# TMK-EURO.net
KiCad netlist of a schematic drawn in EAGLE
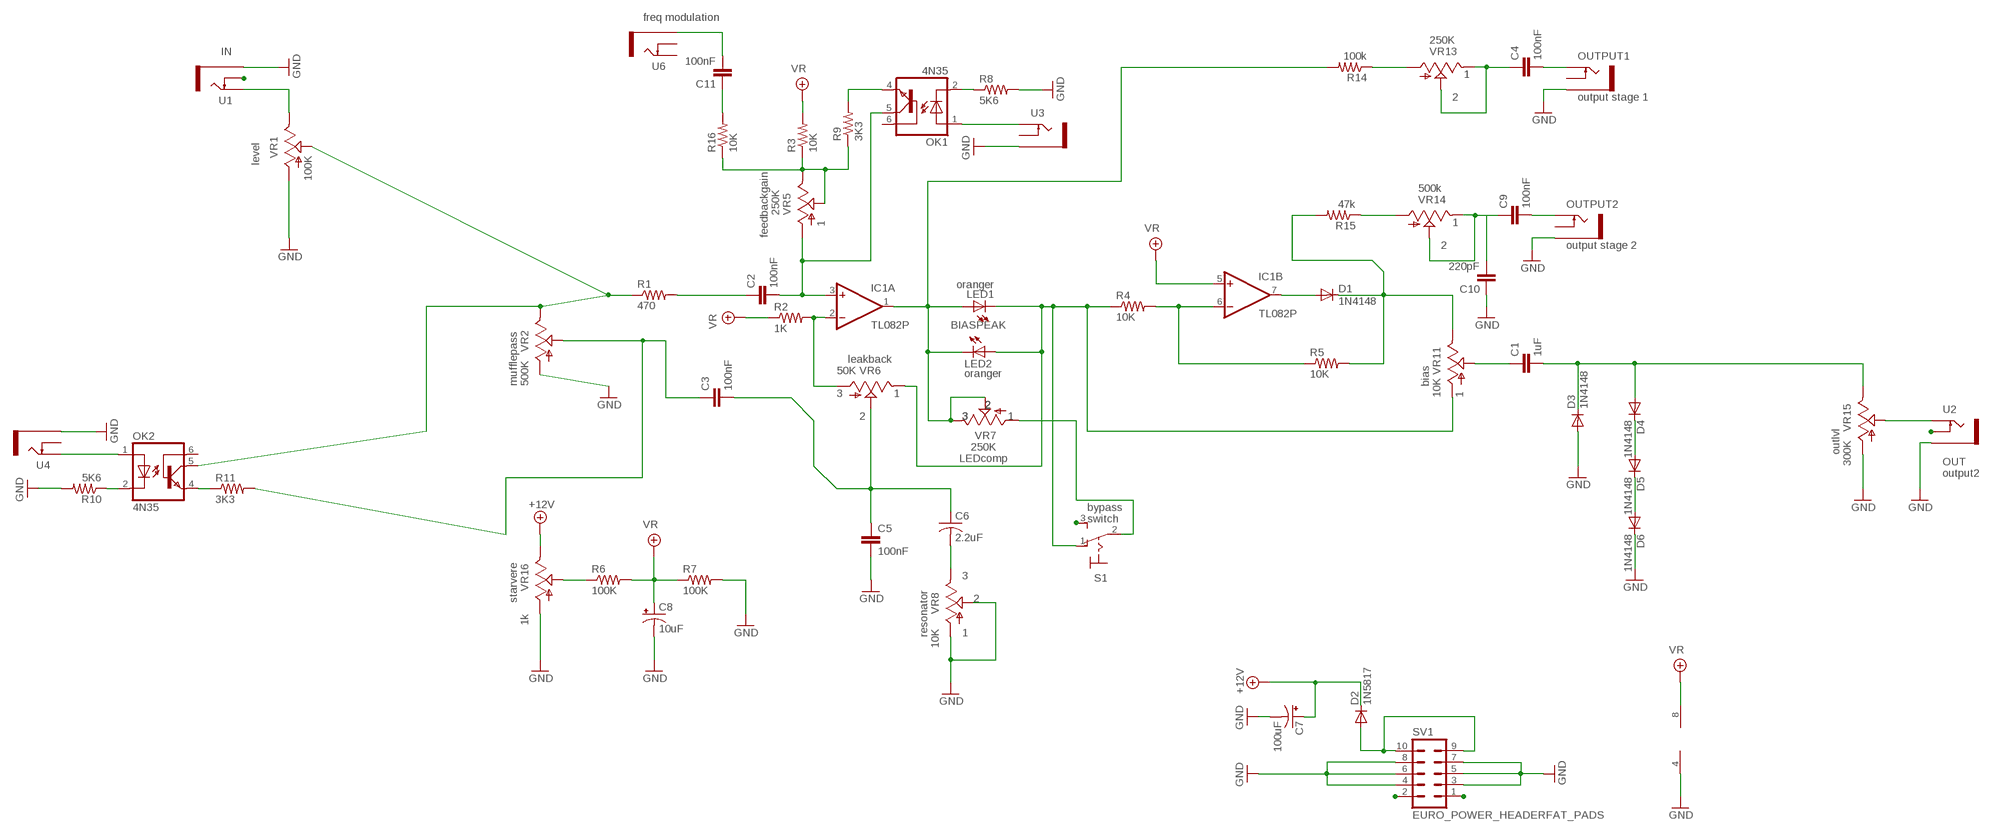
[diagram p0: schematic, sheet 1]

(export (version "E")
  (design (tool "Eeschema 10.0.6"))
  (components
    (comp (ref "C1")
      (value "1uF")
      (footprint "eagle-import:C050-035X075")
      (libsource (lib "eagle-import") (part "C-EU050-035X075"))
    )
    (comp (ref "C2")
      (value "100nF")
      (footprint "eagle-import:C050-035X075")
      (libsource (lib "eagle-import") (part "C-EU050-035X075"))
    )
    (comp (ref "C3")
      (value "100nF")
      (footprint "eagle-import:C050-035X075")
      (libsource (lib "eagle-import") (part "C-EU050-035X075"))
    )
    (comp (ref "C4")
      (value "100nF")
      (footprint "eagle-import:C050-035X075")
      (libsource (lib "eagle-import") (part "C-EU050-035X075"))
    )
    (comp (ref "C5")
      (value "100nF")
      (footprint "eagle-import:C050-035X075")
      (libsource (lib "eagle-import") (part "C-EU050-035X075"))
    )
    (comp (ref "C6")
      (value "2.2uF")
      (footprint "eagle-import:C050-030X075")
      (libsource (lib "eagle-import") (part "C-US050-030X075"))
    )
    (comp (ref "C7")
      (value "100uF")
      (footprint "eagle-import:E2-5")
      (libsource (lib "eagle-import") (part "CPOL-USE2-5"))
    )
    (comp (ref "C8")
      (value "10uF")
      (footprint "eagle-import:E2-5")
      (libsource (lib "eagle-import") (part "CPOL-USE2-5"))
    )
    (comp (ref "C9")
      (value "100nF")
      (footprint "eagle-import:C050-035X075")
      (libsource (lib "eagle-import") (part "C-EU050-035X075"))
    )
    (comp (ref "C10")
      (value "220pF")
      (footprint "eagle-import:C050-035X075")
      (libsource (lib "eagle-import") (part "C-EU050-035X075"))
    )
    (comp (ref "C11")
      (value "100nF")
      (footprint "eagle-import:C050-035X075")
      (libsource (lib "eagle-import") (part "C-EU050-035X075"))
    )
    (comp (ref "D1")
      (value "1N4148")
      (footprint "eagle-import:DO35-7")
      (libsource (lib "eagle-import") (part "SMALL_DIODEDO35-7"))
    )
    (comp (ref "D2")
      (value "1N5817")
      (footprint "eagle-import:DO35-7")
      (libsource (lib "eagle-import") (part "SMALL_DIODEDO35-7"))
    )
    (comp (ref "D3")
      (value "1N4148")
      (footprint "eagle-import:DO35-7")
      (libsource (lib "eagle-import") (part "SMALL_DIODEDO35-7"))
    )
    (comp (ref "D4")
      (value "1N4148")
      (footprint "eagle-import:DO35-7")
      (libsource (lib "eagle-import") (part "SMALL_DIODEDO35-7"))
    )
    (comp (ref "D5")
      (value "1N4148")
      (footprint "eagle-import:DO35-7")
      (libsource (lib "eagle-import") (part "SMALL_DIODEDO35-7"))
    )
    (comp (ref "D6")
      (value "1N4148")
      (footprint "eagle-import:DO35-7")
      (libsource (lib "eagle-import") (part "SMALL_DIODEDO35-7"))
    )
    (comp (ref "IC1")
      (value "TL082P")
      (footprint "eagle-import:DIL08")
      (libsource (lib "eagle-import") (part "TL082P"))
    )
    (comp (ref "LED1")
      (value "oranger")
      (footprint "eagle-import:LED3MM")
      (libsource (lib "eagle-import") (part "LED3MM"))
    )
    (comp (ref "LED2")
      (value "oranger")
      (footprint "eagle-import:LED3MM")
      (libsource (lib "eagle-import") (part "LED3MM"))
    )
    (comp (ref "OK1")
      (value "4N35")
      (footprint "eagle-import:DIL06")
      (fields (field (name "MF") "FAIRCHILD SEMICONDUCTOR"))
      (libsource (lib "eagle-import") (part "4N35"))
    )
    (comp (ref "OK2")
      (value "4N35")
      (footprint "eagle-import:DIL06")
      (fields (field (name "MF") "FAIRCHILD SEMICONDUCTOR"))
      (libsource (lib "eagle-import") (part "4N35"))
    )
    (comp (ref "OUTPUT1")
      (value "IN")
      (footprint "eagle-import:THONKICONN")
      (libsource (lib "eagle-import") (part "THONKICONNOLD"))
    )
    (comp (ref "OUTPUT2")
      (value "IN")
      (footprint "eagle-import:THONKICONN")
      (libsource (lib "eagle-import") (part "THONKICONNOLD"))
    )
    (comp (ref "R1")
      (value "470")
      (footprint "eagle-import:0207_7")
      (libsource (lib "eagle-import") (part "R-US_0207/7"))
    )
    (comp (ref "R2")
      (value "1K")
      (footprint "eagle-import:0207_7")
      (libsource (lib "eagle-import") (part "R-US_0207/7"))
    )
    (comp (ref "R3")
      (value "10K")
      (footprint "eagle-import:0207_7")
      (libsource (lib "eagle-import") (part "R-US_0207/7"))
    )
    (comp (ref "R4")
      (value "10K")
      (footprint "eagle-import:0207_7")
      (libsource (lib "eagle-import") (part "R-US_0207/7"))
    )
    (comp (ref "R5")
      (value "10K")
      (footprint "eagle-import:0207_7")
      (libsource (lib "eagle-import") (part "R-US_0207/7"))
    )
    (comp (ref "R6")
      (value "100K")
      (footprint "eagle-import:0207_7")
      (libsource (lib "eagle-import") (part "R-US_0207/7"))
    )
    (comp (ref "R7")
      (value "100K")
      (footprint "eagle-import:0207_7")
      (libsource (lib "eagle-import") (part "R-US_0207/7"))
    )
    (comp (ref "R8")
      (value "5K6")
      (footprint "eagle-import:0207_7")
      (libsource (lib "eagle-import") (part "R-US_0207/7"))
    )
    (comp (ref "R9")
      (value "3K3")
      (footprint "eagle-import:0207_7")
      (libsource (lib "eagle-import") (part "R-US_0207/7"))
    )
    (comp (ref "R10")
      (value "5K6")
      (footprint "eagle-import:0207_7")
      (libsource (lib "eagle-import") (part "R-US_0207/7"))
    )
    (comp (ref "R11")
      (value "3K3")
      (footprint "eagle-import:0207_7")
      (libsource (lib "eagle-import") (part "R-US_0207/7"))
    )
    (comp (ref "R14")
      (value "100k")
      (footprint "eagle-import:0207_7")
      (libsource (lib "eagle-import") (part "R-US_0207/7"))
    )
    (comp (ref "R15")
      (value "47k")
      (footprint "eagle-import:0207_7")
      (libsource (lib "eagle-import") (part "R-US_0207/7"))
    )
    (comp (ref "R16")
      (value "10K")
      (footprint "eagle-import:0207_7")
      (libsource (lib "eagle-import") (part "R-US_0207/7"))
    )
    (comp (ref "S1")
      (value "320-916")
      (footprint "eagle-import:320-916")
      (libsource (lib "eagle-import") (part "320-916"))
    )
    (comp (ref "SV1")
      (value "EURO_POWER_HEADERFAT_PADS")
      (footprint "eagle-import:EURO_PWR_HEADER_FAT")
      (libsource (lib "eagle-import") (part "EURO_POWER_HEADERFAT_PADS"))
    )
    (comp (ref "U1")
      (value "IN")
      (footprint "eagle-import:THONKICONN")
      (libsource (lib "eagle-import") (part "THONKICONNOLD"))
    )
    (comp (ref "U2")
      (value "THONKICONNOLD")
      (footprint "eagle-import:THONKICONN")
      (libsource (lib "eagle-import") (part "THONKICONNOLD"))
    )
    (comp (ref "U3")
      (value "IN")
      (footprint "eagle-import:THONKICONN")
      (libsource (lib "eagle-import") (part "THONKICONNOLD"))
    )
    (comp (ref "U4")
      (value "IN")
      (footprint "eagle-import:THONKICONN")
      (libsource (lib "eagle-import") (part "THONKICONNOLD"))
    )
    (comp (ref "U6")
      (value "IN")
      (footprint "eagle-import:THONKICONN")
      (libsource (lib "eagle-import") (part "THONKICONNOLD"))
    )
    (comp (ref "VR1")
      (value "100K")
      (footprint "eagle-import:9MM_SNAP-IN_POT")
      (libsource (lib "eagle-import") (part "9MM_SNAP-IN_POT_"))
    )
    (comp (ref "VR2")
      (value "500K")
      (footprint "eagle-import:9MM_SNAP-IN_POT")
      (libsource (lib "eagle-import") (part "9MM_SNAP-IN_POT_"))
    )
    (comp (ref "VR5")
      (value "250K")
      (footprint "eagle-import:9MM_SNAP-IN_POT")
      (libsource (lib "eagle-import") (part "9MM_SNAP-IN_POT_"))
    )
    (comp (ref "VR6")
      (value "50K")
      (footprint "eagle-import:9MM_SNAP-IN_POT")
      (libsource (lib "eagle-import") (part "9MM_SNAP-IN_POT_"))
    )
    (comp (ref "VR7")
      (value "250K")
      (footprint "eagle-import:9MM_SNAP-IN_POT")
      (libsource (lib "eagle-import") (part "9MM_SNAP-IN_POT_"))
    )
    (comp (ref "VR8")
      (value "10K")
      (footprint "eagle-import:9MM_SNAP-IN_POT")
      (libsource (lib "eagle-import") (part "9MM_SNAP-IN_POT_"))
    )
    (comp (ref "VR11")
      (value "10K")
      (footprint "eagle-import:9MM_SNAP-IN_POT")
      (libsource (lib "eagle-import") (part "9MM_SNAP-IN_POT_"))
    )
    (comp (ref "VR13")
      (value "250K")
      (footprint "eagle-import:9MM_SNAP-IN_POT")
      (libsource (lib "eagle-import") (part "9MM_SNAP-IN_POT_"))
    )
    (comp (ref "VR14")
      (value "500k")
      (footprint "eagle-import:9MM_SNAP-IN_POT")
      (libsource (lib "eagle-import") (part "9MM_SNAP-IN_POT_"))
    )
    (comp (ref "VR15")
      (value "300K")
      (footprint "eagle-import:9MM_SNAP-IN_POT")
      (libsource (lib "eagle-import") (part "9MM_SNAP-IN_POT_"))
    )
    (comp (ref "VR16")
      (value "1k")
      (footprint "eagle-import:9MM_SNAP-IN_POT")
      (libsource (lib "eagle-import") (part "9MM_SNAP-IN_POT_"))
    )
  )
  (nets
    (net (code "1") (name "+12V") (class "Default")
      (node (ref "C7") (pin "+") (pinfunction "+_+") (pintype "passive"))
      (node (ref "D2") (pin "C") (pinfunction "C_C") (pintype "passive"))
      (node (ref "VR16") (pin "3") (pinfunction "E_3") (pintype "passive"))
    )
    (net (code "2") (name "GND") (class "Default")
      (node (ref "C10") (pin "1") (pinfunction "1_1") (pintype "passive"))
      (node (ref "C5") (pin "2") (pinfunction "2_2") (pintype "passive"))
      (node (ref "C7") (pin "-") (pinfunction "-_-") (pintype "passive"))
      (node (ref "C8") (pin "-") (pinfunction "-_-") (pintype "passive"))
      (node (ref "D3") (pin "A") (pinfunction "A_A") (pintype "passive"))
      (node (ref "D6") (pin "C") (pinfunction "C_C") (pintype "passive"))
      (node (ref "IC1") (pin "4") (pinfunction "V-_4") (pintype "power_in"))
      (node (ref "OUTPUT1") (pin "P$1_SLEEVE") (pinfunction "SLEEVE_P$1_SLEEVE") (pintype "passive"))
      (node (ref "OUTPUT2") (pin "P$1_SLEEVE") (pinfunction "SLEEVE_P$1_SLEEVE") (pintype "passive"))
      (node (ref "R10") (pin "2") (pinfunction "2_2") (pintype "passive"))
      (node (ref "R7") (pin "2") (pinfunction "2_2") (pintype "passive"))
      (node (ref "R8") (pin "2") (pinfunction "2_2") (pintype "passive"))
      (node (ref "SV1") (pin "3") (pinfunction "3_3") (pintype "passive"))
      (node (ref "SV1") (pin "4") (pinfunction "4_4") (pintype "passive"))
      (node (ref "SV1") (pin "5") (pinfunction "5_5") (pintype "passive"))
      (node (ref "SV1") (pin "6") (pinfunction "6_6") (pintype "passive"))
      (node (ref "SV1") (pin "7") (pinfunction "7_7") (pintype "passive"))
      (node (ref "SV1") (pin "8") (pinfunction "8_8") (pintype "passive"))
      (node (ref "U1") (pin "P$1_SLEEVE") (pinfunction "SLEEVE_P$1_SLEEVE") (pintype "passive"))
      (node (ref "U2") (pin "P$1_SLEEVE") (pinfunction "SLEEVE_P$1_SLEEVE") (pintype "passive"))
      (node (ref "U3") (pin "P$1_SLEEVE") (pinfunction "SLEEVE_P$1_SLEEVE") (pintype "passive"))
      (node (ref "U4") (pin "P$1_SLEEVE") (pinfunction "SLEEVE_P$1_SLEEVE") (pintype "passive"))
      (node (ref "VR1") (pin "1") (pinfunction "A_1") (pintype "passive"))
      (node (ref "VR15") (pin "1") (pinfunction "A_1") (pintype "passive"))
      (node (ref "VR16") (pin "1") (pinfunction "A_1") (pintype "passive"))
      (node (ref "VR2") (pin "1") (pinfunction "A_1") (pintype "passive"))
      (node (ref "VR8") (pin "1") (pinfunction "A_1") (pintype "passive"))
      (node (ref "VR8") (pin "2") (pinfunction "S_2") (pintype "passive"))
    )
    (net (code "3") (name "Net-(C2-Pad1)") (class "Default")
      (node (ref "C2") (pin "1") (pinfunction "1_1") (pintype "passive"))
      (node (ref "R1") (pin "2") (pinfunction "2_2") (pintype "passive"))
    )
    (net (code "4") (name "Net-(C11-Pad1)") (class "Default")
      (node (ref "C11") (pin "1") (pinfunction "1_1") (pintype "passive"))
      (node (ref "R16") (pin "2") (pinfunction "2_2") (pintype "passive"))
    )
    (net (code "5") (name "Net-(D2-PadA)") (class "Default")
      (node (ref "D2") (pin "A") (pinfunction "A_A") (pintype "passive"))
      (node (ref "SV1") (pin "10") (pinfunction "10_10") (pintype "passive"))
      (node (ref "SV1") (pin "9") (pinfunction "9_9") (pintype "passive"))
    )
    (net (code "6") (name "Net-(D4-PadC)") (class "Default")
      (node (ref "D4") (pin "C") (pinfunction "C_C") (pintype "passive"))
      (node (ref "D5") (pin "A") (pinfunction "A_A") (pintype "passive"))
    )
    (net (code "7") (name "Net-(D5-PadC)") (class "Default")
      (node (ref "D5") (pin "C") (pinfunction "C_C") (pintype "passive"))
      (node (ref "D6") (pin "A") (pinfunction "A_A") (pintype "passive"))
    )
    (net (code "8") (name "Net-(IC1A-+IN)") (class "Default")
      (node (ref "C2") (pin "2") (pinfunction "2_2") (pintype "passive"))
      (node (ref "IC1") (pin "3") (pinfunction "+IN_3") (pintype "input"))
      (node (ref "OK1") (pin "5") (pinfunction "COL_5") (pintype "passive"))
      (node (ref "VR5") (pin "1") (pinfunction "A_1") (pintype "passive"))
    )
    (net (code "9") (name "Net-(IC1A--IN)") (class "Default")
      (node (ref "IC1") (pin "2") (pinfunction "-IN_2") (pintype "input"))
      (node (ref "R2") (pin "2") (pinfunction "2_2") (pintype "passive"))
      (node (ref "VR6") (pin "1") (pinfunction "A_1") (pintype "passive"))
    )
    (net (code "10") (name "Net-(IC1A-OUT)") (class "Default")
      (node (ref "IC1") (pin "1") (pinfunction "OUT_1") (pintype "output"))
      (node (ref "LED1") (pin "A") (pinfunction "A_A") (pintype "passive"))
      (node (ref "LED2") (pin "K") (pinfunction "C_K") (pintype "passive"))
      (node (ref "R14") (pin "2") (pinfunction "2_2") (pintype "passive"))
      (node (ref "VR7") (pin "2") (pinfunction "S_2") (pintype "passive"))
      (node (ref "VR7") (pin "3") (pinfunction "E_3") (pintype "passive"))
    )
    (net (code "11") (name "Net-(IC1B--IN)") (class "Default")
      (node (ref "IC1") (pin "6") (pinfunction "-IN_6") (pintype "input"))
      (node (ref "R4") (pin "2") (pinfunction "2_2") (pintype "passive"))
      (node (ref "R5") (pin "1") (pinfunction "1_1") (pintype "passive"))
    )
    (net (code "12") (name "Net-(IC1B-OUT)") (class "Default")
      (node (ref "D1") (pin "A") (pinfunction "A_A") (pintype "passive"))
      (node (ref "IC1") (pin "7") (pinfunction "OUT_7") (pintype "output"))
    )
    (net (code "13") (name "Net-(LED1-C)") (class "Default")
      (node (ref "LED1") (pin "K") (pinfunction "C_K") (pintype "passive"))
      (node (ref "LED2") (pin "A") (pinfunction "A_A") (pintype "passive"))
      (node (ref "R4") (pin "1") (pinfunction "1_1") (pintype "passive"))
      (node (ref "S1") (pin "1") (pinfunction "O_1") (pintype "passive"))
      (node (ref "VR11") (pin "1") (pinfunction "A_1") (pintype "passive"))
      (node (ref "VR6") (pin "3") (pinfunction "E_3") (pintype "passive"))
    )
    (net (code "14") (name "Net-(OK1-A)") (class "Default")
      (node (ref "OK1") (pin "1") (pinfunction "A_1") (pintype "passive"))
      (node (ref "U3") (pin "P$3_TIP") (pinfunction "TIP_P$3_TIP") (pintype "passive"))
    )
    (net (code "15") (name "Net-(OK1-C)") (class "Default")
      (node (ref "OK1") (pin "2") (pinfunction "C_2") (pintype "passive"))
      (node (ref "R8") (pin "1") (pinfunction "1_1") (pintype "passive"))
    )
    (net (code "16") (name "Net-(OK1-EMI)") (class "Default")
      (node (ref "OK1") (pin "4") (pinfunction "EMI_4") (pintype "passive"))
      (node (ref "R9") (pin "2") (pinfunction "2_2") (pintype "passive"))
    )
    (net (code "17") (name "Net-(OK2-A)") (class "Default")
      (node (ref "OK2") (pin "1") (pinfunction "A_1") (pintype "passive"))
      (node (ref "U4") (pin "P$3_TIP") (pinfunction "TIP_P$3_TIP") (pintype "passive"))
    )
    (net (code "18") (name "Net-(OK2-C)") (class "Default")
      (node (ref "OK2") (pin "2") (pinfunction "C_2") (pintype "passive"))
      (node (ref "R10") (pin "1") (pinfunction "1_1") (pintype "passive"))
    )
    (net (code "19") (name "Net-(OK2-COL)") (class "Default")
      (node (ref "OK2") (pin "5") (pinfunction "COL_5") (pintype "passive"))
      (node (ref "R1") (pin "1") (pinfunction "1_1") (pintype "passive"))
      (node (ref "VR1") (pin "2") (pinfunction "S_2") (pintype "passive"))
      (node (ref "VR2") (pin "3") (pinfunction "E_3") (pintype "passive"))
    )
    (net (code "20") (name "Net-(OK2-EMI)") (class "Default")
      (node (ref "OK2") (pin "4") (pinfunction "EMI_4") (pintype "passive"))
      (node (ref "R11") (pin "1") (pinfunction "1_1") (pintype "passive"))
    )
    (net (code "21") (name "Net-(OUTPUT1-TIP)") (class "Default")
      (node (ref "C4") (pin "2") (pinfunction "2_2") (pintype "passive"))
      (node (ref "OUTPUT1") (pin "P$3_TIP") (pinfunction "TIP_P$3_TIP") (pintype "passive"))
    )
    (net (code "22") (name "Net-(OUTPUT2-TIP)") (class "Default")
      (node (ref "C9") (pin "2") (pinfunction "2_2") (pintype "passive"))
      (node (ref "OUTPUT2") (pin "P$3_TIP") (pinfunction "TIP_P$3_TIP") (pintype "passive"))
    )
    (net (code "23") (name "Net-(S1-P)") (class "Default")
      (node (ref "S1") (pin "2") (pinfunction "P_2") (pintype "passive"))
      (node (ref "VR7") (pin "1") (pinfunction "A_1") (pintype "passive"))
    )
    (net (code "24") (name "Net-(U1-TIP)") (class "Default")
      (node (ref "U1") (pin "P$3_TIP") (pinfunction "TIP_P$3_TIP") (pintype "passive"))
      (node (ref "VR1") (pin "3") (pinfunction "E_3") (pintype "passive"))
    )
    (net (code "25") (name "Net-(U2-TIP)") (class "Default")
      (node (ref "U2") (pin "P$3_TIP") (pinfunction "TIP_P$3_TIP") (pintype "passive"))
      (node (ref "VR15") (pin "2") (pinfunction "S_2") (pintype "passive"))
    )
    (net (code "26") (name "Net-(U6-SLEEVE)") (class "Default")
      (node (ref "C11") (pin "2") (pinfunction "2_2") (pintype "passive"))
      (node (ref "U6") (pin "P$1_SLEEVE") (pinfunction "SLEEVE_P$1_SLEEVE") (pintype "passive"))
    )
    (net (code "27") (name "Net-(VR2-S)") (class "Default")
      (node (ref "C3") (pin "1") (pinfunction "1_1") (pintype "passive"))
      (node (ref "R11") (pin "2") (pinfunction "2_2") (pintype "passive"))
      (node (ref "VR2") (pin "2") (pinfunction "S_2") (pintype "passive"))
    )
    (net (code "28") (name "Net-(VR5-E)") (class "Default")
      (node (ref "R16") (pin "1") (pinfunction "1_1") (pintype "passive"))
      (node (ref "R3") (pin "1") (pinfunction "1_1") (pintype "passive"))
      (node (ref "R9") (pin "1") (pinfunction "1_1") (pintype "passive"))
      (node (ref "VR5") (pin "2") (pinfunction "S_2") (pintype "passive"))
      (node (ref "VR5") (pin "3") (pinfunction "E_3") (pintype "passive"))
    )
    (net (code "29") (name "Net-(VR6-S)") (class "Default")
      (node (ref "C3") (pin "2") (pinfunction "2_2") (pintype "passive"))
      (node (ref "C5") (pin "1") (pinfunction "1_1") (pintype "passive"))
      (node (ref "C6") (pin "1") (pinfunction "1_1") (pintype "passive"))
      (node (ref "VR6") (pin "2") (pinfunction "S_2") (pintype "passive"))
    )
    (net (code "30") (name "Net-(VR8-E)") (class "Default")
      (node (ref "C6") (pin "2") (pinfunction "2_2") (pintype "passive"))
      (node (ref "VR8") (pin "3") (pinfunction "E_3") (pintype "passive"))
    )
    (net (code "31") (name "Net-(VR11-E)") (class "Default")
      (node (ref "D1") (pin "C") (pinfunction "C_C") (pintype "passive"))
      (node (ref "R15") (pin "2") (pinfunction "2_2") (pintype "passive"))
      (node (ref "R5") (pin "2") (pinfunction "2_2") (pintype "passive"))
      (node (ref "VR11") (pin "3") (pinfunction "E_3") (pintype "passive"))
    )
    (net (code "32") (name "Net-(VR11-S)") (class "Default")
      (node (ref "C1") (pin "1") (pinfunction "1_1") (pintype "passive"))
      (node (ref "VR11") (pin "2") (pinfunction "S_2") (pintype "passive"))
    )
    (net (code "33") (name "Net-(VR13-A)") (class "Default")
      (node (ref "R14") (pin "1") (pinfunction "1_1") (pintype "passive"))
      (node (ref "VR13") (pin "1") (pinfunction "A_1") (pintype "passive"))
    )
    (net (code "34") (name "Net-(VR13-E)") (class "Default")
      (node (ref "C4") (pin "1") (pinfunction "1_1") (pintype "passive"))
      (node (ref "VR13") (pin "2") (pinfunction "S_2") (pintype "passive"))
      (node (ref "VR13") (pin "3") (pinfunction "E_3") (pintype "passive"))
    )
    (net (code "35") (name "Net-(VR14-A)") (class "Default")
      (node (ref "R15") (pin "1") (pinfunction "1_1") (pintype "passive"))
      (node (ref "VR14") (pin "1") (pinfunction "A_1") (pintype "passive"))
    )
    (net (code "36") (name "Net-(VR14-E)") (class "Default")
      (node (ref "C10") (pin "2") (pinfunction "2_2") (pintype "passive"))
      (node (ref "C9") (pin "1") (pinfunction "1_1") (pintype "passive"))
      (node (ref "VR14") (pin "2") (pinfunction "S_2") (pintype "passive"))
      (node (ref "VR14") (pin "3") (pinfunction "E_3") (pintype "passive"))
    )
    (net (code "37") (name "Net-(VR15-E)") (class "Default")
      (node (ref "C1") (pin "2") (pinfunction "2_2") (pintype "passive"))
      (node (ref "D3") (pin "C") (pinfunction "C_C") (pintype "passive"))
      (node (ref "D4") (pin "A") (pinfunction "A_A") (pintype "passive"))
      (node (ref "VR15") (pin "3") (pinfunction "E_3") (pintype "passive"))
    )
    (net (code "38") (name "Net-(VR16-S)") (class "Default")
      (node (ref "R6") (pin "1") (pinfunction "1_1") (pintype "passive"))
      (node (ref "VR16") (pin "2") (pinfunction "S_2") (pintype "passive"))
    )
    (net (code "39") (name "VR") (class "Default")
      (node (ref "C8") (pin "+") (pinfunction "+_+") (pintype "passive"))
      (node (ref "IC1") (pin "5") (pinfunction "+IN_5") (pintype "input"))
      (node (ref "IC1") (pin "8") (pinfunction "V+_8") (pintype "power_in"))
      (node (ref "R2") (pin "1") (pinfunction "1_1") (pintype "passive"))
      (node (ref "R3") (pin "2") (pinfunction "2_2") (pintype "passive"))
      (node (ref "R6") (pin "2") (pinfunction "2_2") (pintype "passive"))
      (node (ref "R7") (pin "1") (pinfunction "1_1") (pintype "passive"))
    )
    (net (code "40") (name "unconnected-(OK1-BAS-Pad6)") (class "Default")
      (node (ref "OK1") (pin "6") (pinfunction "BAS_6") (pintype "passive"))
    )
    (net (code "41") (name "unconnected-(OK2-BAS-Pad6)") (class "Default")
      (node (ref "OK2") (pin "6") (pinfunction "BAS_6") (pintype "passive"))
    )
    (net (code "42") (name "unconnected-(OUTPUT1-SWITCH-PadP$2_SWITCH)") (class "Default")
      (node (ref "OUTPUT1") (pin "P$2_SWITCH") (pinfunction "SWITCH_P$2_SWITCH") (pintype "passive"))
    )
    (net (code "43") (name "unconnected-(OUTPUT2-SWITCH-PadP$2_SWITCH)") (class "Default")
      (node (ref "OUTPUT2") (pin "P$2_SWITCH") (pinfunction "SWITCH_P$2_SWITCH") (pintype "passive"))
    )
    (net (code "44") (name "unconnected-(S1-S-Pad3)") (class "Default")
      (node (ref "S1") (pin "3") (pinfunction "S_3") (pintype "passive"))
    )
    (net (code "45") (name "unconnected-(SV1-Pad1)") (class "Default")
      (node (ref "SV1") (pin "1") (pinfunction "1_1") (pintype "passive"))
    )
    (net (code "46") (name "unconnected-(SV1-Pad2)") (class "Default")
      (node (ref "SV1") (pin "2") (pinfunction "2_2") (pintype "passive"))
    )
    (net (code "47") (name "unconnected-(U1-SWITCH-PadP$2_SWITCH)") (class "Default")
      (node (ref "U1") (pin "P$2_SWITCH") (pinfunction "SWITCH_P$2_SWITCH") (pintype "passive"))
    )
    (net (code "48") (name "unconnected-(U2-SWITCH-PadP$2_SWITCH)") (class "Default")
      (node (ref "U2") (pin "P$2_SWITCH") (pinfunction "SWITCH_P$2_SWITCH") (pintype "passive"))
    )
    (net (code "49") (name "unconnected-(U3-SWITCH-PadP$2_SWITCH)") (class "Default")
      (node (ref "U3") (pin "P$2_SWITCH") (pinfunction "SWITCH_P$2_SWITCH") (pintype "passive"))
    )
    (net (code "50") (name "unconnected-(U4-SWITCH-PadP$2_SWITCH)") (class "Default")
      (node (ref "U4") (pin "P$2_SWITCH") (pinfunction "SWITCH_P$2_SWITCH") (pintype "passive"))
    )
    (net (code "51") (name "unconnected-(U6-SWITCH-PadP$2_SWITCH)") (class "Default")
      (node (ref "U6") (pin "P$2_SWITCH") (pinfunction "SWITCH_P$2_SWITCH") (pintype "passive"))
    )
    (net (code "52") (name "unconnected-(U6-TIP-PadP$3_TIP)") (class "Default")
      (node (ref "U6") (pin "P$3_TIP") (pinfunction "TIP_P$3_TIP") (pintype "passive"))
    )
  )
)
